# Out_Inputs.net
KiCad netlist of a schematic drawn in Altium Designer
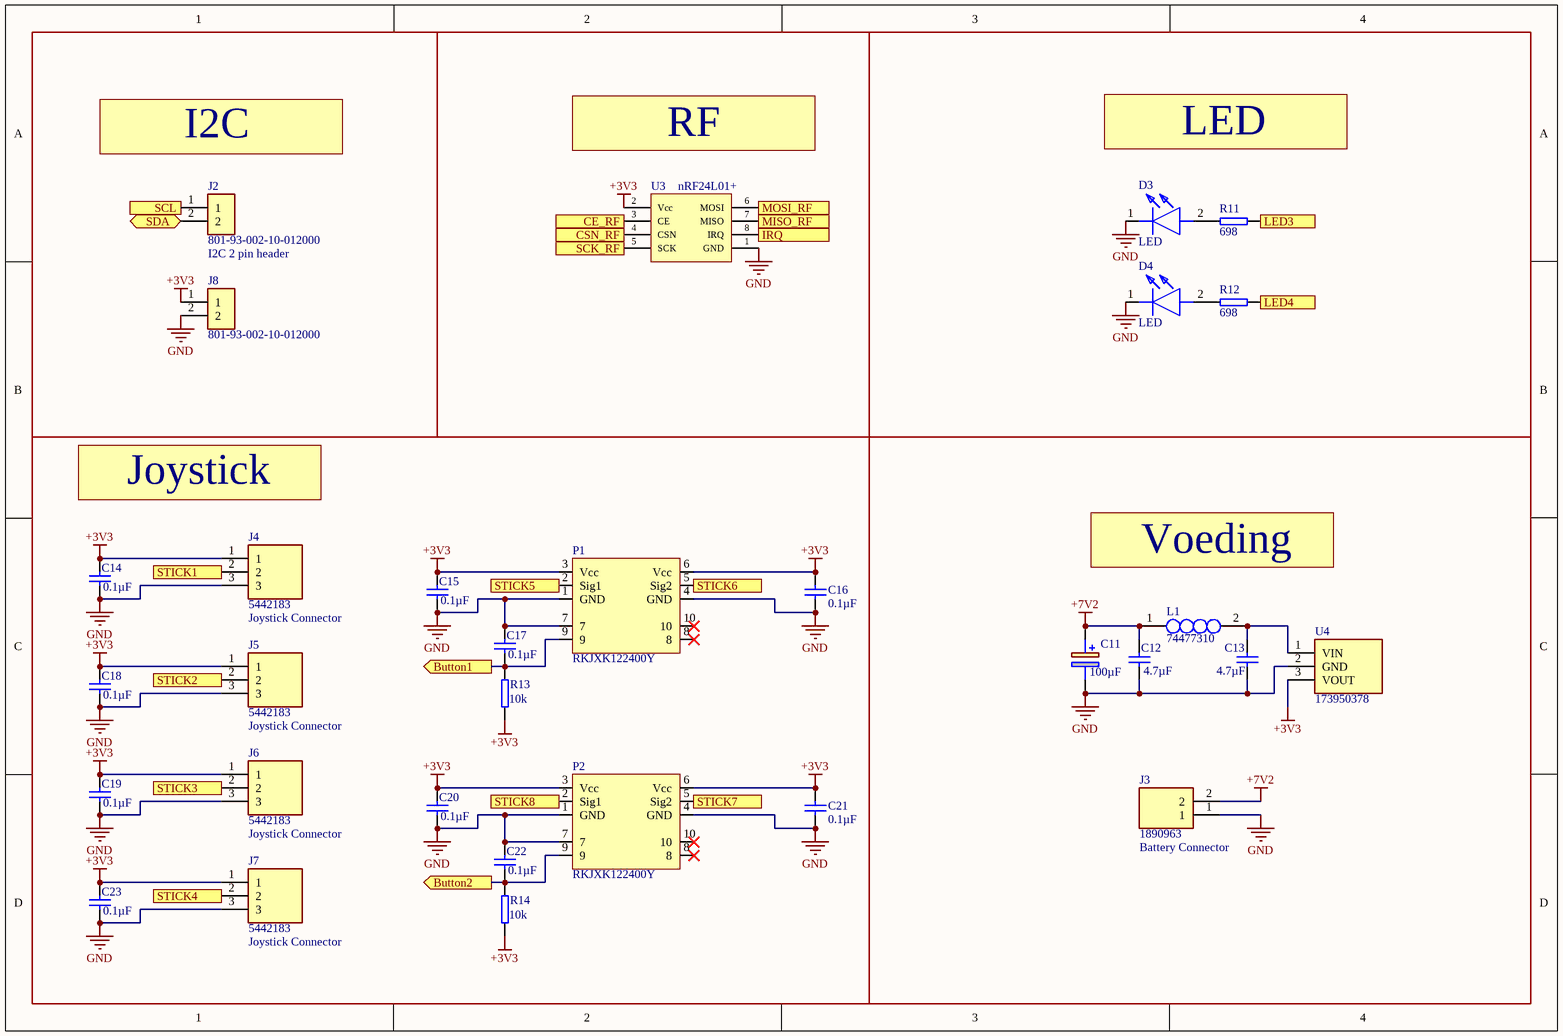
[diagram p0: Out_Inputs.SchDoc]

(export (version "E")
  (design (tool "Eeschema 10.0.6"))
  (components
    (comp (ref "C11")
      (value "100µF")
      (footprint "CAPPRD350W52D800H1300")
      (description "Wurth Elektronik 100uF 50 V dc Aluminium Electrolytic Capacitor")
      (fields
        (field (name "MOUSER PART NUMBER") "710-865080543009")
        (field (name "MANUFACTURER_PART_NUMBER") "865080543009")
      )
      (libsource (lib "Schematic_Lib") (part "860010674014"))
    )
    (comp (ref "C12")
      (value "4.7µF")
      (footprint "Capacitor 1206")
      (description "Capacitor")
      (libsource (lib "Schematic_Lib") (part "Capacitor 1206"))
    )
    (comp (ref "C13")
      (value "4.7µF")
      (footprint "Capacitor 1206")
      (description "Capacitor")
      (libsource (lib "Schematic_Lib") (part "Capacitor 1206"))
    )
    (comp (ref "C14")
      (value "0.1µF")
      (footprint "Capacitor 0603")
      (description "Capacitor")
      (libsource (lib "Schematic_Lib") (part "Capacitor 0603"))
    )
    (comp (ref "C15")
      (value "0.1µF")
      (footprint "Capacitor 0603")
      (description "Capacitor")
      (libsource (lib "Schematic_Lib") (part "Capacitor 0603"))
    )
    (comp (ref "C16")
      (value "0.1µF")
      (footprint "Capacitor 0603")
      (description "Capacitor")
      (libsource (lib "Schematic_Lib") (part "Capacitor 0603"))
    )
    (comp (ref "C17")
      (value "0.1µF")
      (footprint "Capacitor 0603")
      (description "Capacitor")
      (libsource (lib "Schematic_Lib") (part "Capacitor 0603"))
    )
    (comp (ref "C18")
      (value "0.1µF")
      (footprint "Capacitor 0603")
      (description "Capacitor")
      (libsource (lib "Schematic_Lib") (part "Capacitor 0603"))
    )
    (comp (ref "C19")
      (value "0.1µF")
      (footprint "Capacitor 0603")
      (description "Capacitor")
      (libsource (lib "Schematic_Lib") (part "Capacitor 0603"))
    )
    (comp (ref "C20")
      (value "0.1µF")
      (footprint "Capacitor 0603")
      (description "Capacitor")
      (libsource (lib "Schematic_Lib") (part "Capacitor 0603"))
    )
    (comp (ref "C21")
      (value "0.1µF")
      (footprint "Capacitor 0603")
      (description "Capacitor")
      (libsource (lib "Schematic_Lib") (part "Capacitor 0603"))
    )
    (comp (ref "C22")
      (value "0.1µF")
      (footprint "Capacitor 0603")
      (description "Capacitor")
      (libsource (lib "Schematic_Lib") (part "Capacitor 0603"))
    )
    (comp (ref "C23")
      (value "0.1µF")
      (footprint "Capacitor 0603")
      (description "Capacitor")
      (libsource (lib "Schematic_Lib") (part "Capacitor 0603"))
    )
    (comp (ref "D3") (value "LED") (footprint "HLMP-4740") (libsource (lib "Schematic_Lib") (part "LED")))
    (comp (ref "D4") (value "LED") (footprint "HLMP-4740") (libsource (lib "Schematic_Lib") (part "LED")))
    (comp (ref "J2")
      (value "801-93-002-10-012000")
      (footprint "801-93-002-10-012000")
      (description "2 pin header 2.54mm pitch")
      (libsource (lib "Schematic_Lib") (part "801-93-002-10-012000"))
    )
    (comp (ref "J3")
      (value "1890963")
      (footprint "1890963")
      (description "Connector: 2pin screw terminal")
      (fields (field (name "MOUSER PART NUMBER") "651-1890963"))
      (libsource (lib "Schematic_Lib") (part "1890963"))
    )
    (comp (ref "J4")
      (value "5442183")
      (footprint "SamacSys:5442183")
      (description "Connector")
      (fields (field (name "MOUSER PART NUMBER") "651-5442183"))
      (libsource (lib "SamacSys") (part "5442183"))
    )
    (comp (ref "J5")
      (value "5442183")
      (footprint "SamacSys:5442183")
      (description "Connector")
      (fields (field (name "MOUSER PART NUMBER") "651-5442183"))
      (libsource (lib "SamacSys") (part "5442183"))
    )
    (comp (ref "J6")
      (value "5442183")
      (footprint "SamacSys:5442183")
      (description "Connector")
      (fields (field (name "MOUSER PART NUMBER") "651-5442183"))
      (libsource (lib "SamacSys") (part "5442183"))
    )
    (comp (ref "J7")
      (value "5442183")
      (footprint "SamacSys:5442183")
      (description "Connector")
      (fields (field (name "MOUSER PART NUMBER") "651-5442183"))
      (libsource (lib "SamacSys") (part "5442183"))
    )
    (comp (ref "J8")
      (value "801-93-002-10-012000")
      (footprint "801-93-002-10-012000")
      (description "2 pin header 2.54mm pitch")
      (libsource (lib "Schematic_Lib") (part "801-93-002-10-012000"))
    )
    (comp (ref "L1")
      (value "74477310")
      (footprint "WE-PD2_453255")
      (description "Inductor")
      (fields
        (field (name "MANUFACTURER_PART_NUMBER") "7447730")
        (field (name "MOUSER PART NUMBER") "710-7447730")
      )
      (libsource (lib "Schematic_Lib") (part "7447730"))
    )
    (comp (ref "P1")
      (value "RKJXK122400Y")
      (footprint "RKJXK122400Y")
      (libsource (lib "Schematic_Lib") (part "RKJXK122400Y"))
    )
    (comp (ref "P2")
      (value "RKJXK122400Y")
      (footprint "RKJXK122400Y")
      (libsource (lib "Schematic_Lib") (part "RKJXK122400Y"))
    )
    (comp (ref "R11")
      (value "698")
      (footprint "Resistor 0603")
      (description "Resistor")
      (libsource (lib "Schematic_Lib") (part "Resistor 0603"))
    )
    (comp (ref "R12")
      (value "698")
      (footprint "Resistor 0603")
      (description "Resistor")
      (libsource (lib "Schematic_Lib") (part "Resistor 0603"))
    )
    (comp (ref "R13")
      (value "10k")
      (footprint "Resistor 0603")
      (description "Resistor")
      (libsource (lib "Schematic_Lib") (part "Resistor 0603"))
    )
    (comp (ref "R14")
      (value "10k")
      (footprint "Resistor 0603")
      (description "Resistor")
      (libsource (lib "Schematic_Lib") (part "Resistor 0603"))
    )
    (comp (ref "U3")
      (value "nRF24L01+")
      (footprint "nRF24L01+")
      (libsource (lib "Schematic_Lib") (part "nRF24L01+"))
    )
    (comp (ref "U4")
      (value "173950378")
      (footprint "173950378")
      (description "MagI3C Power Module 0.5A 3.3V 6-28V SIP3")
      (fields (field (name "MOUSER PART NUMBER") "710-173950378"))
      (libsource (lib "Schematic_Lib") (part "173950378"))
    )
  )
  (nets
    (net (code "1") (name "+3V3") (class "Default")
      (node (ref "C14") (pin "1") (pinfunction "1_1") (pintype "passive"))
      (node (ref "C15") (pin "1") (pinfunction "1_1") (pintype "passive"))
      (node (ref "C16") (pin "1") (pinfunction "1_1") (pintype "passive"))
      (node (ref "C18") (pin "1") (pinfunction "1_1") (pintype "passive"))
      (node (ref "C19") (pin "1") (pinfunction "1_1") (pintype "passive"))
      (node (ref "C20") (pin "1") (pinfunction "1_1") (pintype "passive"))
      (node (ref "C21") (pin "1") (pinfunction "1_1") (pintype "passive"))
      (node (ref "C23") (pin "1") (pinfunction "1_1") (pintype "passive"))
      (node (ref "J4") (pin "1") (pinfunction "1_1") (pintype "passive"))
      (node (ref "J5") (pin "1") (pinfunction "1_1") (pintype "passive"))
      (node (ref "J6") (pin "1") (pinfunction "1_1") (pintype "passive"))
      (node (ref "J7") (pin "1") (pinfunction "1_1") (pintype "passive"))
      (node (ref "J8") (pin "1") (pinfunction "1_1") (pintype "passive"))
      (node (ref "P1") (pin "3") (pinfunction "Vcc_3") (pintype "passive"))
      (node (ref "P1") (pin "6") (pinfunction "Vcc_6") (pintype "passive"))
      (node (ref "P2") (pin "3") (pinfunction "Vcc_3") (pintype "passive"))
      (node (ref "P2") (pin "6") (pinfunction "Vcc_6") (pintype "passive"))
      (node (ref "R13") (pin "2") (pintype "passive"))
      (node (ref "R14") (pin "2") (pintype "passive"))
      (node (ref "U3") (pin "2") (pinfunction "Vcc_2") (pintype "passive"))
      (node (ref "U4") (pin "3") (pinfunction "VOUT_3") (pintype "passive"))
    )
    (net (code "2") (name "+7V2") (class "Default")
      (node (ref "C11") (pin "1") (pinfunction "+_1") (pintype "passive"))
      (node (ref "C12") (pin "1") (pinfunction "1_1") (pintype "passive"))
      (node (ref "J3") (pin "2") (pinfunction "2_2") (pintype "passive"))
      (node (ref "L1") (pin "1") (pinfunction "1_1") (pintype "passive"))
    )
    (net (code "3") (name "/Button1") (class "Default")
      (node (ref "C17") (pin "2") (pinfunction "2_2") (pintype "passive"))
      (node (ref "P1") (pin "9") (pinfunction "9_9") (pintype "passive"))
      (node (ref "R13") (pin "1") (pintype "passive"))
    )
    (net (code "4") (name "/Button2") (class "Default")
      (node (ref "C22") (pin "2") (pinfunction "2_2") (pintype "passive"))
      (node (ref "P2") (pin "9") (pinfunction "9_9") (pintype "passive"))
      (node (ref "R14") (pin "1") (pintype "passive"))
    )
    (net (code "5") (name "/CE_RF") (class "Default")
      (node (ref "U3") (pin "3") (pinfunction "CE_3") (pintype "passive"))
    )
    (net (code "6") (name "/CSN_RF") (class "Default")
      (node (ref "U3") (pin "4") (pinfunction "CSN_4") (pintype "passive"))
    )
    (net (code "7") (name "/IRQ") (class "Default")
      (node (ref "U3") (pin "8") (pinfunction "IRQ_8") (pintype "passive"))
    )
    (net (code "8") (name "/LED3") (class "Default") (node (ref "R11") (pin "1") (pintype "passive")))
    (net (code "9") (name "/LED4") (class "Default") (node (ref "R12") (pin "1") (pintype "passive")))
    (net (code "10") (name "/MISO_RF") (class "Default")
      (node (ref "U3") (pin "7") (pinfunction "MISO_7") (pintype "passive"))
    )
    (net (code "11") (name "/MOSI_RF") (class "Default")
      (node (ref "U3") (pin "6") (pinfunction "MOSI_6") (pintype "passive"))
    )
    (net (code "12") (name "/SCK_RF") (class "Default")
      (node (ref "U3") (pin "5") (pinfunction "SCK_5") (pintype "passive"))
    )
    (net (code "13") (name "/SCL") (class "Default")
      (node (ref "J2") (pin "1") (pinfunction "1_1") (pintype "passive"))
    )
    (net (code "14") (name "/SDA") (class "Default")
      (node (ref "J2") (pin "2") (pinfunction "2_2") (pintype "passive"))
    )
    (net (code "15") (name "/STICK1") (class "Default")
      (node (ref "J4") (pin "2") (pinfunction "2_2") (pintype "passive"))
    )
    (net (code "16") (name "/STICK2") (class "Default")
      (node (ref "J5") (pin "2") (pinfunction "2_2") (pintype "passive"))
    )
    (net (code "17") (name "/STICK3") (class "Default")
      (node (ref "J6") (pin "2") (pinfunction "2_2") (pintype "passive"))
    )
    (net (code "18") (name "/STICK4") (class "Default")
      (node (ref "J7") (pin "2") (pinfunction "2_2") (pintype "passive"))
    )
    (net (code "19") (name "/STICK5") (class "Default")
      (node (ref "P1") (pin "2") (pinfunction "Sig1_2") (pintype "passive"))
    )
    (net (code "20") (name "/STICK6") (class "Default")
      (node (ref "P1") (pin "5") (pinfunction "Sig2_5") (pintype "passive"))
    )
    (net (code "21") (name "/STICK7") (class "Default")
      (node (ref "P2") (pin "5") (pinfunction "Sig2_5") (pintype "passive"))
    )
    (net (code "22") (name "/STICK8") (class "Default")
      (node (ref "P2") (pin "2") (pinfunction "Sig1_2") (pintype "passive"))
    )
    (net (code "23") (name "GND") (class "Default")
      (node (ref "C11") (pin "2") (pinfunction "-_2") (pintype "passive"))
      (node (ref "C12") (pin "2") (pinfunction "2_2") (pintype "passive"))
      (node (ref "C13") (pin "2") (pinfunction "2_2") (pintype "passive"))
      (node (ref "C14") (pin "2") (pinfunction "2_2") (pintype "passive"))
      (node (ref "C15") (pin "2") (pinfunction "2_2") (pintype "passive"))
      (node (ref "C16") (pin "2") (pinfunction "2_2") (pintype "passive"))
      (node (ref "C17") (pin "1") (pinfunction "1_1") (pintype "passive"))
      (node (ref "C18") (pin "2") (pinfunction "2_2") (pintype "passive"))
      (node (ref "C19") (pin "2") (pinfunction "2_2") (pintype "passive"))
      (node (ref "C20") (pin "2") (pinfunction "2_2") (pintype "passive"))
      (node (ref "C21") (pin "2") (pinfunction "2_2") (pintype "passive"))
      (node (ref "C22") (pin "1") (pinfunction "1_1") (pintype "passive"))
      (node (ref "C23") (pin "2") (pinfunction "2_2") (pintype "passive"))
      (node (ref "D3") (pin "1") (pinfunction "K_1") (pintype "passive"))
      (node (ref "D4") (pin "1") (pinfunction "K_1") (pintype "passive"))
      (node (ref "J3") (pin "1") (pinfunction "1_1") (pintype "passive"))
      (node (ref "J4") (pin "3") (pinfunction "3_3") (pintype "passive"))
      (node (ref "J5") (pin "3") (pinfunction "3_3") (pintype "passive"))
      (node (ref "J6") (pin "3") (pinfunction "3_3") (pintype "passive"))
      (node (ref "J7") (pin "3") (pinfunction "3_3") (pintype "passive"))
      (node (ref "J8") (pin "2") (pinfunction "2_2") (pintype "passive"))
      (node (ref "P1") (pin "1") (pinfunction "GND_1") (pintype "passive"))
      (node (ref "P1") (pin "4") (pinfunction "GND_4") (pintype "passive"))
      (node (ref "P1") (pin "7") (pinfunction "7_7") (pintype "passive"))
      (node (ref "P2") (pin "1") (pinfunction "GND_1") (pintype "passive"))
      (node (ref "P2") (pin "4") (pinfunction "GND_4") (pintype "passive"))
      (node (ref "P2") (pin "7") (pinfunction "7_7") (pintype "passive"))
      (node (ref "U3") (pin "1") (pinfunction "GND_1") (pintype "passive"))
      (node (ref "U4") (pin "2") (pinfunction "GND_2") (pintype "passive"))
    )
    (net (code "24") (name "Net-(D3-A)") (class "Default")
      (node (ref "D3") (pin "2") (pinfunction "A_2") (pintype "passive"))
      (node (ref "R11") (pin "2") (pintype "passive"))
    )
    (net (code "25") (name "Net-(D4-A)") (class "Default")
      (node (ref "D4") (pin "2") (pinfunction "A_2") (pintype "passive"))
      (node (ref "R12") (pin "2") (pintype "passive"))
    )
    (net (code "26") (name "Net-(U4-VIN)") (class "Default")
      (node (ref "C13") (pin "1") (pinfunction "1_1") (pintype "passive"))
      (node (ref "L1") (pin "2") (pinfunction "2_2") (pintype "passive"))
      (node (ref "U4") (pin "1") (pinfunction "VIN_1") (pintype "passive"))
    )
    (net (code "27") (name "unconnected-(P1-Pad8)") (class "Default")
      (node (ref "P1") (pin "8") (pinfunction "8_8") (pintype "passive+no_connect"))
    )
    (net (code "28") (name "unconnected-(P1-Pad10)") (class "Default")
      (node (ref "P1") (pin "10") (pinfunction "10_10") (pintype "passive+no_connect"))
    )
    (net (code "29") (name "unconnected-(P2-Pad8)") (class "Default")
      (node (ref "P2") (pin "8") (pinfunction "8_8") (pintype "passive+no_connect"))
    )
    (net (code "30") (name "unconnected-(P2-Pad10)") (class "Default")
      (node (ref "P2") (pin "10") (pinfunction "10_10") (pintype "passive+no_connect"))
    )
  )
)
